# STM32.net
KiCad netlist of a schematic drawn in Altium Designer
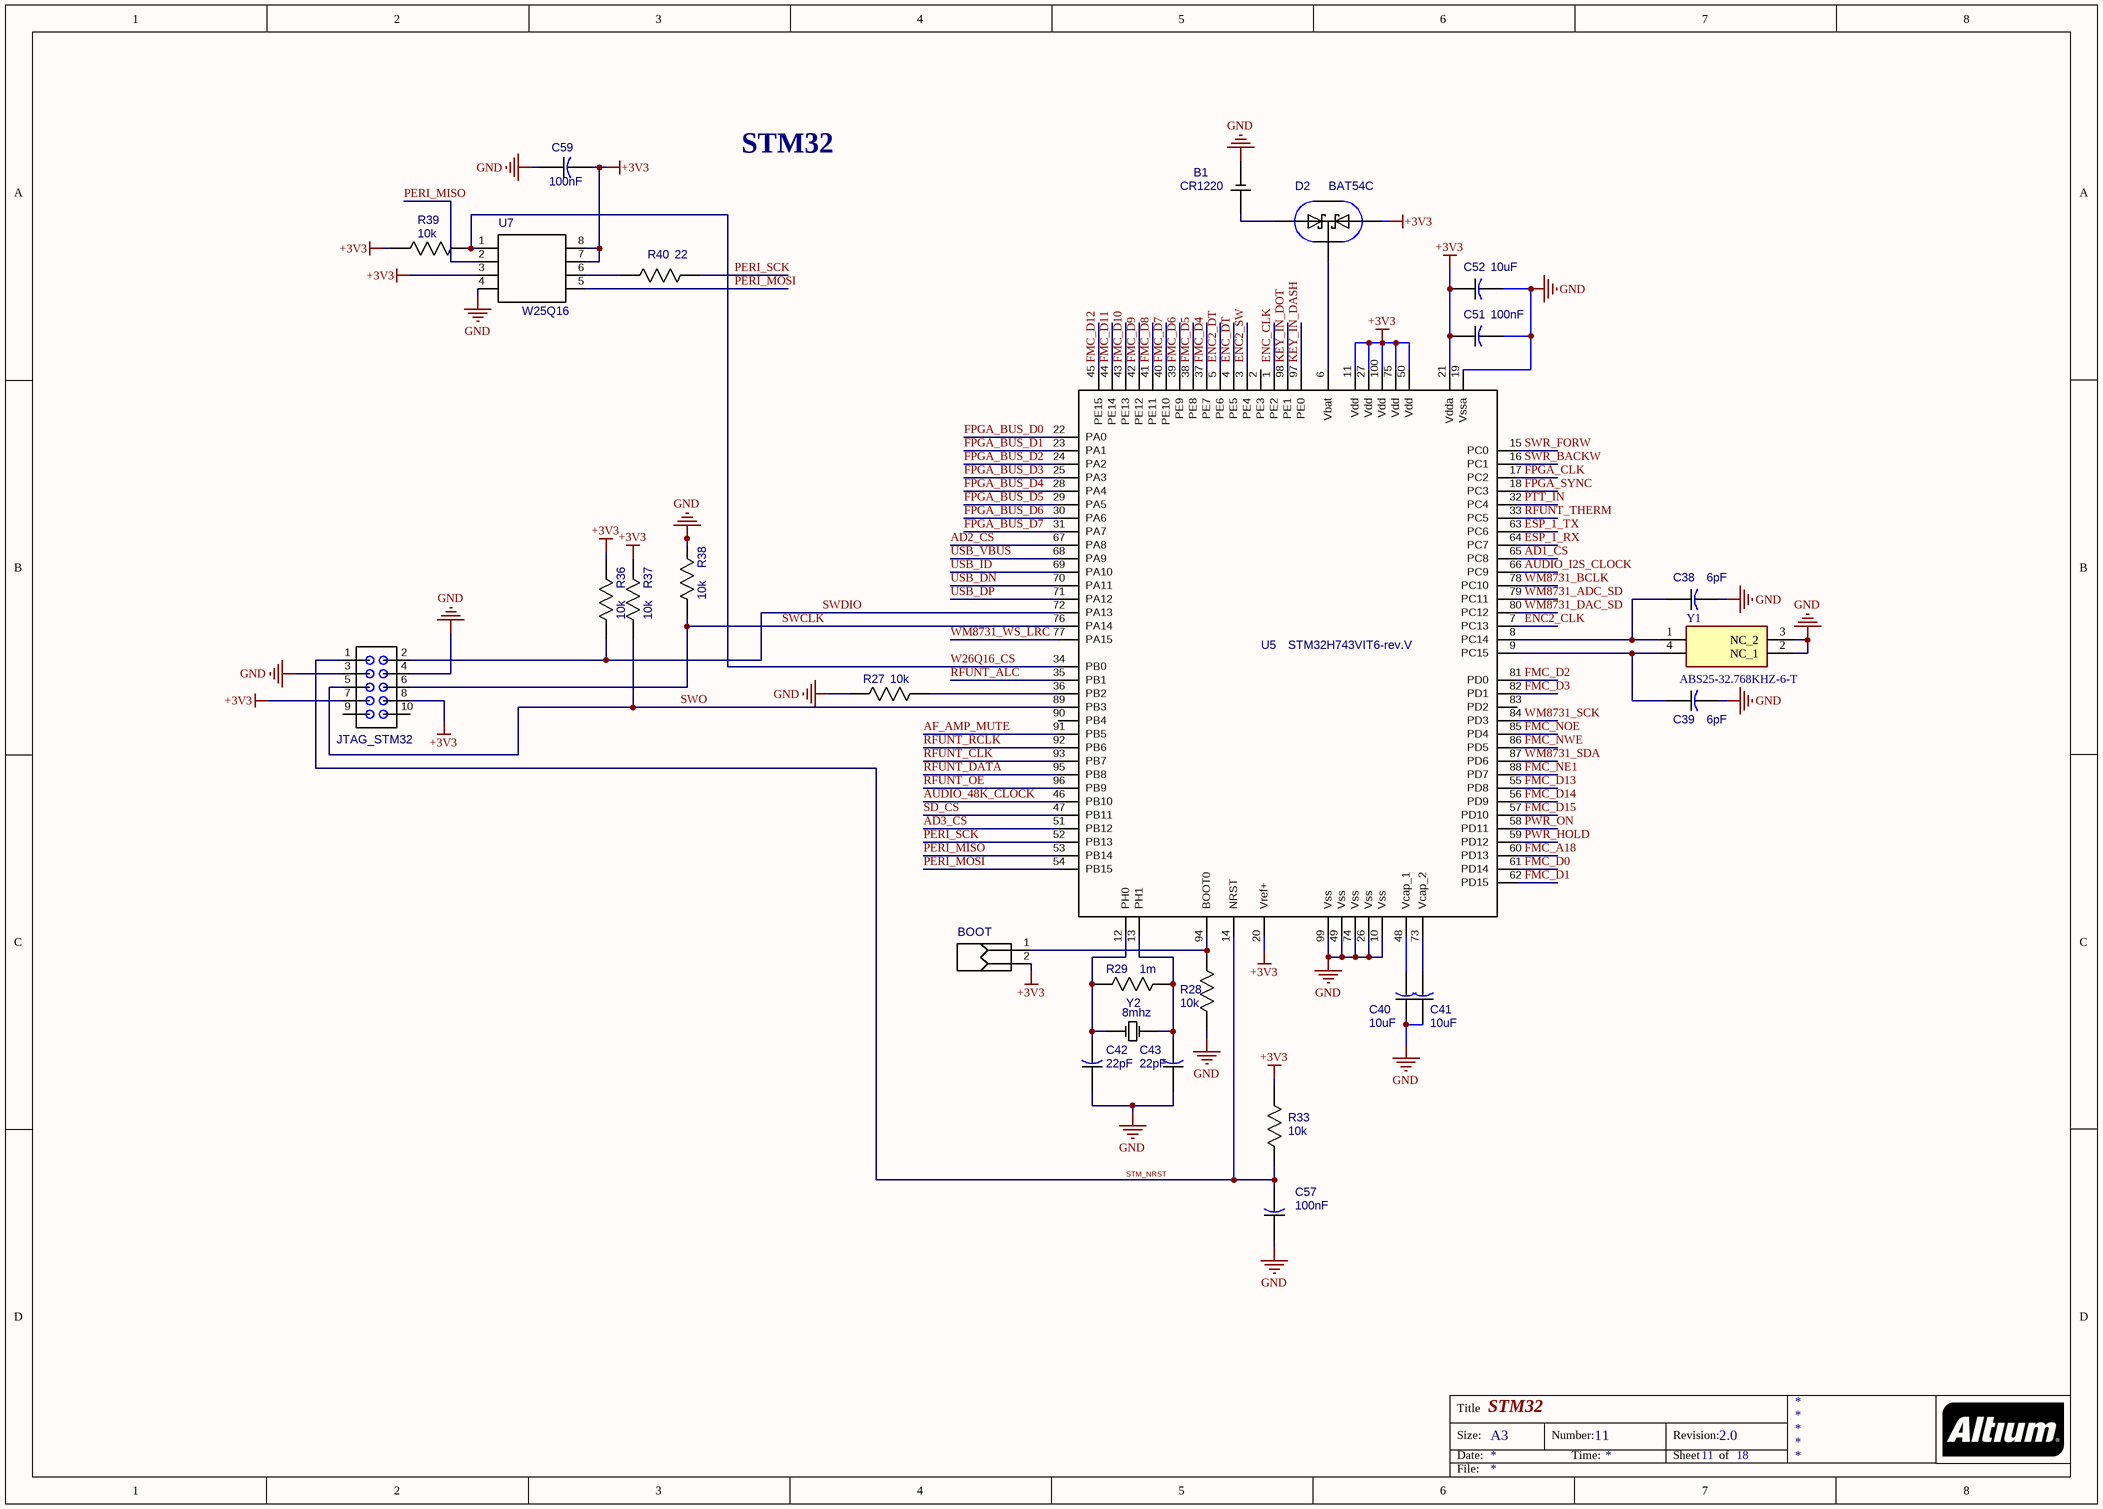
[diagram p0: STM32.SchDoc]

(export (version "E")
  (design (tool "Eeschema 10.0.6"))
  (components
    (comp (ref "B1")
      (value "CR1220")
      (footprint "KLS5-CR1220-01")
      (description "BR1632A/FA")
      (libsource (lib "*") (part "BR1632A/FA"))
    )
    (comp (ref "BOOT")
      (value "~")
      (footprint "51022-0200")
      (description "2 Pin")
      (libsource (lib "*") (part "51022-0200"))
    )
    (comp (ref "C38")
      (value "6pF")
      (footprint "CAP_0805")
      (description "CAP_0805")
      (libsource (lib "*") (part "CAP_0805"))
    )
    (comp (ref "C39")
      (value "6pF")
      (footprint "CAP_0805")
      (description "CAP_0805")
      (libsource (lib "*") (part "CAP_0805"))
    )
    (comp (ref "C40")
      (value "10uF")
      (footprint "CAP_0805")
      (description "CAP_0805")
      (libsource (lib "*") (part "CAP_0805"))
    )
    (comp (ref "C41")
      (value "10uF")
      (footprint "CAP_0805")
      (description "CAP_0805")
      (libsource (lib "*") (part "CAP_0805"))
    )
    (comp (ref "C42")
      (value "22pF")
      (footprint "CAP_0805")
      (description "CAP_0805")
      (libsource (lib "*") (part "CAP_0805"))
    )
    (comp (ref "C43")
      (value "22pF")
      (footprint "CAP_0805")
      (description "CAP_0805")
      (libsource (lib "*") (part "CAP_0805"))
    )
    (comp (ref "C51")
      (value "100nF")
      (footprint "CAP_0805")
      (description "CAP_0805")
      (libsource (lib "*") (part "CAP_0805"))
    )
    (comp (ref "C52")
      (value "10uF")
      (footprint "CAP_0805")
      (description "CAP_0805")
      (libsource (lib "*") (part "CAP_0805"))
    )
    (comp (ref "C57")
      (value "100nF")
      (footprint "CAP_0805")
      (description "CAP_0805")
      (libsource (lib "*") (part "CAP_0805"))
    )
    (comp (ref "C59")
      (value "100nF")
      (footprint "CAP_0805")
      (description "CAP_0805")
      (libsource (lib "*") (part "CAP_0805"))
    )
    (comp (ref "D2") (value "BAT54C") (footprint "BAT54C") (libsource (lib "*") (part "BAT54C")))
    (comp (ref "JTAG_STM32")
      (value "~")
      (footprint "IDC10")
      (description "2*5 Pin")
      (libsource (lib "*") (part "IDC10"))
    )
    (comp (ref "R27")
      (value "10k")
      (footprint "RES_0805")
      (description "RES_0805")
      (libsource (lib "*") (part "RES_0805"))
    )
    (comp (ref "R28")
      (value "10k")
      (footprint "RES_0805")
      (description "RES_0805")
      (libsource (lib "*") (part "RES_0805"))
    )
    (comp (ref "R29")
      (value "1m")
      (footprint "RES_0805")
      (description "RES_0805")
      (libsource (lib "*") (part "RES_0805"))
    )
    (comp (ref "R33")
      (value "10k")
      (footprint "RES_0805")
      (description "RES_0805")
      (libsource (lib "*") (part "RES_0805"))
    )
    (comp (ref "R36")
      (value "10k")
      (footprint "RES_0805")
      (description "RES_0805")
      (libsource (lib "*") (part "RES_0805"))
    )
    (comp (ref "R37")
      (value "10k")
      (footprint "RES_0805")
      (description "RES_0805")
      (libsource (lib "*") (part "RES_0805"))
    )
    (comp (ref "R38")
      (value "10k")
      (footprint "RES_0805")
      (description "RES_0805")
      (libsource (lib "*") (part "RES_0805"))
    )
    (comp (ref "R39")
      (value "10k")
      (footprint "RES_0805")
      (description "RES_0805")
      (libsource (lib "*") (part "RES_0805"))
    )
    (comp (ref "R40")
      (value "22")
      (footprint "RES_0805")
      (description "RES_0805")
      (libsource (lib "*") (part "RES_0805"))
    )
    (comp (ref "U5")
      (value "STM32H743VIT6-rev.V")
      (footprint "STM32H743VIT6")
      (description "STM32H743VIT6")
      (libsource (lib "*") (part "STM32H743VIT6"))
    )
    (comp (ref "U7") (value "W25Q16") (footprint "W25Q16") (libsource (lib "*") (part "W25Q16")))
    (comp (ref "Y1")
      (value "ABS25-32.768KHZ-6-T")
      (footprint "SamacSys:ABS25")
      (description "Crystal or Oscillator")
      (fields
        (field (name "MOUSER PART NUMBER") "815-ABS25-32.768K6-T")
        (field (name "RS PART NUMBER") "1712795P")
      )
      (libsource (lib "*") (part "ABS25-32.768KHZ-6-T"))
    )
    (comp (ref "Y2")
      (value "8mhz")
      (footprint "ECS-200-20-1")
      (description "ECS-200-20-1")
      (libsource (lib "*") (part "ECS-200-20-1"))
    )
  )
  (nets
    (net (code "1") (name "+3V3") (class "Default")
      (node (ref "BOOT") (pin "2") (pinfunction "2_2") (pintype "passive"))
      (node (ref "C51") (pin "1") (pinfunction "1_1") (pintype "passive"))
      (node (ref "C52") (pin "1") (pinfunction "1_1") (pintype "passive"))
      (node (ref "C59") (pin "2") (pinfunction "2_2") (pintype "passive"))
      (node (ref "D2") (pin "1") (pinfunction "(A1)_1") (pintype "passive"))
      (node (ref "JTAG_STM32") (pin "7") (pinfunction "7_7") (pintype "passive"))
      (node (ref "JTAG_STM32") (pin "8") (pinfunction "8_8") (pintype "passive"))
      (node (ref "R33") (pin "2") (pinfunction "2_2") (pintype "passive"))
      (node (ref "R36") (pin "1") (pinfunction "1_1") (pintype "passive"))
      (node (ref "R37") (pin "1") (pinfunction "1_1") (pintype "passive"))
      (node (ref "R39") (pin "1") (pinfunction "1_1") (pintype "passive"))
      (node (ref "U5") (pin "100") (pinfunction "Vdd_100") (pintype "passive"))
      (node (ref "U5") (pin "11") (pinfunction "Vdd_11") (pintype "passive"))
      (node (ref "U5") (pin "20") (pinfunction "Vref+_20") (pintype "passive"))
      (node (ref "U5") (pin "21") (pinfunction "Vdda_21") (pintype "passive"))
      (node (ref "U5") (pin "27") (pinfunction "Vdd_27") (pintype "passive"))
      (node (ref "U5") (pin "50") (pinfunction "Vdd_50") (pintype "passive"))
      (node (ref "U5") (pin "75") (pinfunction "Vdd_75") (pintype "passive"))
      (node (ref "U7") (pin "3") (pinfunction "WP_3") (pintype "passive"))
      (node (ref "U7") (pin "7") (pinfunction "HOLD_7") (pintype "passive"))
      (node (ref "U7") (pin "8") (pinfunction "VCC_8") (pintype "passive"))
    )
    (net (code "2") (name "/AD1_CS") (class "Default")
      (node (ref "U5") (pin "65") (pinfunction "PC8_65") (pintype "passive"))
    )
    (net (code "3") (name "/AD2_CS") (class "Default")
      (node (ref "U5") (pin "67") (pinfunction "PA8_67") (pintype "passive"))
    )
    (net (code "4") (name "/AD3_CS") (class "Default")
      (node (ref "U5") (pin "51") (pinfunction "PB12_51") (pintype "passive"))
    )
    (net (code "5") (name "/AF_AMP_MUTE") (class "Default")
      (node (ref "U5") (pin "91") (pinfunction "PB5_91") (pintype "passive"))
    )
    (net (code "6") (name "/AUDIO_48K_CLOCK") (class "Default")
      (node (ref "U5") (pin "46") (pinfunction "PB10_46") (pintype "passive"))
    )
    (net (code "7") (name "/AUDIO_I2S_CLOCK") (class "Default")
      (node (ref "U5") (pin "66") (pinfunction "PC9_66") (pintype "passive"))
    )
    (net (code "8") (name "/ENC2_CLK") (class "Default")
      (node (ref "U5") (pin "7") (pinfunction "PC13_7") (pintype "passive"))
    )
    (net (code "9") (name "/ENC2_DT") (class "Default")
      (node (ref "U5") (pin "5") (pinfunction "PE6_5") (pintype "passive"))
    )
    (net (code "10") (name "/ENC2_SW") (class "Default")
      (node (ref "U5") (pin "3") (pinfunction "PE4_3") (pintype "passive"))
    )
    (net (code "11") (name "/ENC_CLK") (class "Default")
      (node (ref "U5") (pin "1") (pinfunction "PE2_1") (pintype "passive"))
    )
    (net (code "12") (name "/ENC_DT") (class "Default")
      (node (ref "U5") (pin "4") (pinfunction "PE5_4") (pintype "passive"))
    )
    (net (code "13") (name "/ESP_1_RX") (class "Default")
      (node (ref "U5") (pin "64") (pinfunction "PC7_64") (pintype "passive"))
    )
    (net (code "14") (name "/ESP_1_TX") (class "Default")
      (node (ref "U5") (pin "63") (pinfunction "PC6_63") (pintype "passive"))
    )
    (net (code "15") (name "/FMC_A18") (class "Default")
      (node (ref "U5") (pin "60") (pinfunction "PD13_60") (pintype "passive"))
    )
    (net (code "16") (name "/FMC_D0") (class "Default")
      (node (ref "U5") (pin "61") (pinfunction "PD14_61") (pintype "passive"))
    )
    (net (code "17") (name "/FMC_D1") (class "Default")
      (node (ref "U5") (pin "62") (pinfunction "PD15_62") (pintype "passive"))
    )
    (net (code "18") (name "/FMC_D2") (class "Default")
      (node (ref "U5") (pin "81") (pinfunction "PD0_81") (pintype "passive"))
    )
    (net (code "19") (name "/FMC_D3") (class "Default")
      (node (ref "U5") (pin "82") (pinfunction "PD1_82") (pintype "passive"))
    )
    (net (code "20") (name "/FMC_D4") (class "Default")
      (node (ref "U5") (pin "37") (pinfunction "PE7_37") (pintype "passive"))
    )
    (net (code "21") (name "/FMC_D5") (class "Default")
      (node (ref "U5") (pin "38") (pinfunction "PE8_38") (pintype "passive"))
    )
    (net (code "22") (name "/FMC_D6") (class "Default")
      (node (ref "U5") (pin "39") (pinfunction "PE9_39") (pintype "passive"))
    )
    (net (code "23") (name "/FMC_D7") (class "Default")
      (node (ref "U5") (pin "40") (pinfunction "PE10_40") (pintype "passive"))
    )
    (net (code "24") (name "/FMC_D8") (class "Default")
      (node (ref "U5") (pin "41") (pinfunction "PE11_41") (pintype "passive"))
    )
    (net (code "25") (name "/FMC_D9") (class "Default")
      (node (ref "U5") (pin "42") (pinfunction "PE12_42") (pintype "passive"))
    )
    (net (code "26") (name "/FMC_D10") (class "Default")
      (node (ref "U5") (pin "43") (pinfunction "PE13_43") (pintype "passive"))
    )
    (net (code "27") (name "/FMC_D11") (class "Default")
      (node (ref "U5") (pin "44") (pinfunction "PE14_44") (pintype "passive"))
    )
    (net (code "28") (name "/FMC_D12") (class "Default")
      (node (ref "U5") (pin "45") (pinfunction "PE15_45") (pintype "passive"))
    )
    (net (code "29") (name "/FMC_D13") (class "Default")
      (node (ref "U5") (pin "55") (pinfunction "PD8_55") (pintype "passive"))
    )
    (net (code "30") (name "/FMC_D14") (class "Default")
      (node (ref "U5") (pin "56") (pinfunction "PD9_56") (pintype "passive"))
    )
    (net (code "31") (name "/FMC_D15") (class "Default")
      (node (ref "U5") (pin "57") (pinfunction "PD10_57") (pintype "passive"))
    )
    (net (code "32") (name "/FMC_NE1") (class "Default")
      (node (ref "U5") (pin "88") (pinfunction "PD7_88") (pintype "passive"))
    )
    (net (code "33") (name "/FMC_NOE") (class "Default")
      (node (ref "U5") (pin "85") (pinfunction "PD4_85") (pintype "passive"))
    )
    (net (code "34") (name "/FMC_NWE") (class "Default")
      (node (ref "U5") (pin "86") (pinfunction "PD5_86") (pintype "passive"))
    )
    (net (code "35") (name "/FPGA_BUS_D0") (class "Default")
      (node (ref "U5") (pin "22") (pinfunction "PA0_22") (pintype "passive"))
    )
    (net (code "36") (name "/FPGA_BUS_D1") (class "Default")
      (node (ref "U5") (pin "23") (pinfunction "PA1_23") (pintype "passive"))
    )
    (net (code "37") (name "/FPGA_BUS_D2") (class "Default")
      (node (ref "U5") (pin "24") (pinfunction "PA2_24") (pintype "passive"))
    )
    (net (code "38") (name "/FPGA_BUS_D3") (class "Default")
      (node (ref "U5") (pin "25") (pinfunction "PA3_25") (pintype "passive"))
    )
    (net (code "39") (name "/FPGA_BUS_D4") (class "Default")
      (node (ref "U5") (pin "28") (pinfunction "PA4_28") (pintype "passive"))
    )
    (net (code "40") (name "/FPGA_BUS_D5") (class "Default")
      (node (ref "U5") (pin "29") (pinfunction "PA5_29") (pintype "passive"))
    )
    (net (code "41") (name "/FPGA_BUS_D6") (class "Default")
      (node (ref "U5") (pin "30") (pinfunction "PA6_30") (pintype "passive"))
    )
    (net (code "42") (name "/FPGA_BUS_D7") (class "Default")
      (node (ref "U5") (pin "31") (pinfunction "PA7_31") (pintype "passive"))
    )
    (net (code "43") (name "/FPGA_CLK") (class "Default")
      (node (ref "U5") (pin "17") (pinfunction "PC2_17") (pintype "passive"))
    )
    (net (code "44") (name "/FPGA_SYNC") (class "Default")
      (node (ref "U5") (pin "18") (pinfunction "PC3_18") (pintype "passive"))
    )
    (net (code "45") (name "/KEY_IN_DASH") (class "Default")
      (node (ref "U5") (pin "97") (pinfunction "PE0_97") (pintype "passive"))
    )
    (net (code "46") (name "/KEY_IN_DOT") (class "Default")
      (node (ref "U5") (pin "98") (pinfunction "PE1_98") (pintype "passive"))
    )
    (net (code "47") (name "/PERI_MISO") (class "Default")
      (node (ref "U5") (pin "53") (pinfunction "PB14_53") (pintype "passive"))
      (node (ref "U7") (pin "2") (pinfunction "SO_2") (pintype "passive"))
    )
    (net (code "48") (name "/PERI_MOSI") (class "Default")
      (node (ref "U5") (pin "54") (pinfunction "PB15_54") (pintype "passive"))
      (node (ref "U7") (pin "5") (pinfunction "SI_5") (pintype "passive"))
    )
    (net (code "49") (name "/PERI_SCK") (class "Default")
      (node (ref "R40") (pin "2") (pinfunction "2_2") (pintype "passive"))
      (node (ref "U5") (pin "52") (pinfunction "PB13_52") (pintype "passive"))
    )
    (net (code "50") (name "/PTT_IN") (class "Default")
      (node (ref "U5") (pin "32") (pinfunction "PC4_32") (pintype "passive"))
    )
    (net (code "51") (name "/PWR_HOLD") (class "Default")
      (node (ref "U5") (pin "59") (pinfunction "PD12_59") (pintype "passive"))
    )
    (net (code "52") (name "/PWR_ON") (class "Default")
      (node (ref "U5") (pin "58") (pinfunction "PD11_58") (pintype "passive"))
    )
    (net (code "53") (name "/RFUNT_ALC") (class "Default")
      (node (ref "U5") (pin "35") (pinfunction "PB1_35") (pintype "passive"))
    )
    (net (code "54") (name "/RFUNT_CLK") (class "Default")
      (node (ref "U5") (pin "93") (pinfunction "PB7_93") (pintype "passive"))
    )
    (net (code "55") (name "/RFUNT_DATA") (class "Default")
      (node (ref "U5") (pin "95") (pinfunction "PB8_95") (pintype "passive"))
    )
    (net (code "56") (name "/RFUNT_OE") (class "Default")
      (node (ref "U5") (pin "96") (pinfunction "PB9_96") (pintype "passive"))
    )
    (net (code "57") (name "/RFUNT_RCLK") (class "Default")
      (node (ref "U5") (pin "92") (pinfunction "PB6_92") (pintype "passive"))
    )
    (net (code "58") (name "/RFUNT_THERM") (class "Default")
      (node (ref "U5") (pin "33") (pinfunction "PC5_33") (pintype "passive"))
    )
    (net (code "59") (name "/SD_CS") (class "Default")
      (node (ref "U5") (pin "47") (pinfunction "PB11_47") (pintype "passive"))
    )
    (net (code "60") (name "/STM_NRST") (class "Default")
      (node (ref "C57") (pin "2") (pinfunction "2_2") (pintype "passive"))
      (node (ref "JTAG_STM32") (pin "1") (pinfunction "1_1") (pintype "passive"))
      (node (ref "R33") (pin "1") (pinfunction "1_1") (pintype "passive"))
      (node (ref "U5") (pin "14") (pinfunction "NRST_14") (pintype "passive"))
    )
    (net (code "61") (name "/SWCLK") (class "Default")
      (node (ref "JTAG_STM32") (pin "6") (pinfunction "6_6") (pintype "passive"))
      (node (ref "R38") (pin "2") (pinfunction "2_2") (pintype "passive"))
      (node (ref "U5") (pin "76") (pinfunction "PA14_76") (pintype "passive"))
    )
    (net (code "62") (name "/SWDIO") (class "Default")
      (node (ref "JTAG_STM32") (pin "2") (pinfunction "2_2") (pintype "passive"))
      (node (ref "R36") (pin "2") (pinfunction "2_2") (pintype "passive"))
      (node (ref "U5") (pin "72") (pinfunction "PA13_72") (pintype "passive"))
    )
    (net (code "63") (name "/SWO") (class "Default")
      (node (ref "JTAG_STM32") (pin "5") (pinfunction "5_5") (pintype "passive"))
      (node (ref "R37") (pin "2") (pinfunction "2_2") (pintype "passive"))
      (node (ref "U5") (pin "89") (pinfunction "PB3_89") (pintype "passive"))
    )
    (net (code "64") (name "/SWR_BACKW") (class "Default")
      (node (ref "U5") (pin "16") (pinfunction "PC1_16") (pintype "passive"))
    )
    (net (code "65") (name "/SWR_FORW") (class "Default")
      (node (ref "U5") (pin "15") (pinfunction "PC0_15") (pintype "passive"))
    )
    (net (code "66") (name "/USB_DN") (class "Default")
      (node (ref "U5") (pin "70") (pinfunction "PA11_70") (pintype "passive"))
    )
    (net (code "67") (name "/USB_DP") (class "Default")
      (node (ref "U5") (pin "71") (pinfunction "PA12_71") (pintype "passive"))
    )
    (net (code "68") (name "/USB_ID") (class "Default")
      (node (ref "U5") (pin "69") (pinfunction "PA10_69") (pintype "passive"))
    )
    (net (code "69") (name "/USB_VBUS") (class "Default")
      (node (ref "U5") (pin "68") (pinfunction "PA9_68") (pintype "passive"))
    )
    (net (code "70") (name "/W26Q16_CS") (class "Default")
      (node (ref "R39") (pin "2") (pinfunction "2_2") (pintype "passive"))
      (node (ref "U5") (pin "34") (pinfunction "PB0_34") (pintype "passive"))
      (node (ref "U7") (pin "1") (pinfunction "CS_1") (pintype "passive"))
    )
    (net (code "71") (name "/WM8731_ADC_SD") (class "Default")
      (node (ref "U5") (pin "79") (pinfunction "PC11_79") (pintype "passive"))
    )
    (net (code "72") (name "/WM8731_BCLK") (class "Default")
      (node (ref "U5") (pin "78") (pinfunction "PC10_78") (pintype "passive"))
    )
    (net (code "73") (name "/WM8731_DAC_SD") (class "Default")
      (node (ref "U5") (pin "80") (pinfunction "PC12_80") (pintype "passive"))
    )
    (net (code "74") (name "/WM8731_SCK") (class "Default")
      (node (ref "U5") (pin "84") (pinfunction "PD3_84") (pintype "passive"))
    )
    (net (code "75") (name "/WM8731_SDA") (class "Default")
      (node (ref "U5") (pin "87") (pinfunction "PD6_87") (pintype "passive"))
    )
    (net (code "76") (name "/WM8731_WS_LRC") (class "Default")
      (node (ref "U5") (pin "77") (pinfunction "PA15_77") (pintype "passive"))
    )
    (net (code "77") (name "GND") (class "Default")
      (node (ref "B1") (pin "2") (pinfunction "NEG_2") (pintype "passive"))
      (node (ref "C38") (pin "2") (pinfunction "2_2") (pintype "passive"))
      (node (ref "C39") (pin "2") (pinfunction "2_2") (pintype "passive"))
      (node (ref "C40") (pin "1") (pinfunction "1_1") (pintype "passive"))
      (node (ref "C41") (pin "1") (pinfunction "1_1") (pintype "passive"))
      (node (ref "C42") (pin "1") (pinfunction "1_1") (pintype "passive"))
      (node (ref "C43") (pin "1") (pinfunction "1_1") (pintype "passive"))
      (node (ref "C51") (pin "2") (pinfunction "2_2") (pintype "passive"))
      (node (ref "C52") (pin "2") (pinfunction "2_2") (pintype "passive"))
      (node (ref "C57") (pin "1") (pinfunction "1_1") (pintype "passive"))
      (node (ref "C59") (pin "1") (pinfunction "1_1") (pintype "passive"))
      (node (ref "JTAG_STM32") (pin "3") (pinfunction "3_3") (pintype "passive"))
      (node (ref "JTAG_STM32") (pin "4") (pinfunction "4_4") (pintype "passive"))
      (node (ref "R27") (pin "1") (pinfunction "1_1") (pintype "passive"))
      (node (ref "R28") (pin "1") (pinfunction "1_1") (pintype "passive"))
      (node (ref "R38") (pin "1") (pinfunction "1_1") (pintype "passive"))
      (node (ref "U5") (pin "10") (pinfunction "Vss_10") (pintype "passive"))
      (node (ref "U5") (pin "19") (pinfunction "Vssa_19") (pintype "passive"))
      (node (ref "U5") (pin "26") (pinfunction "Vss_26") (pintype "passive"))
      (node (ref "U5") (pin "49") (pinfunction "Vss_49") (pintype "passive"))
      (node (ref "U5") (pin "74") (pinfunction "Vss_74") (pintype "passive"))
      (node (ref "U5") (pin "99") (pinfunction "Vss_99") (pintype "passive"))
      (node (ref "U7") (pin "4") (pinfunction "GND_4") (pintype "passive"))
      (node (ref "Y1") (pin "2") (pinfunction "NC_1_2") (pintype "passive"))
      (node (ref "Y1") (pin "3") (pinfunction "NC_2_3") (pintype "passive"))
    )
    (net (code "78") (name "Net-(B1-POS)") (class "Default")
      (node (ref "B1") (pin "1") (pinfunction "POS_1") (pintype "passive"))
      (node (ref "D2") (pin "2") (pinfunction "(A2)_2") (pintype "passive"))
    )
    (net (code "79") (name "Net-(D2-(K1),(K2))") (class "Default")
      (node (ref "D2") (pin "3") (pinfunction "(K1),(K2)_3") (pintype "passive"))
      (node (ref "U5") (pin "6") (pinfunction "Vbat_6") (pintype "passive"))
    )
    (net (code "80") (name "Net-(U5-BOOT0)") (class "Default")
      (node (ref "BOOT") (pin "1") (pinfunction "1_1") (pintype "passive"))
      (node (ref "R28") (pin "2") (pinfunction "2_2") (pintype "passive"))
      (node (ref "U5") (pin "94") (pinfunction "BOOT0_94") (pintype "passive"))
    )
    (net (code "81") (name "Net-(U5-PB2)") (class "Default")
      (node (ref "R27") (pin "2") (pinfunction "2_2") (pintype "passive"))
      (node (ref "U5") (pin "36") (pinfunction "PB2_36") (pintype "passive"))
    )
    (net (code "82") (name "Net-(U5-PC14)") (class "Default")
      (node (ref "C38") (pin "1") (pinfunction "1_1") (pintype "passive"))
      (node (ref "U5") (pin "8") (pinfunction "PC14_8") (pintype "passive"))
      (node (ref "Y1") (pin "1") (pinfunction "1_1") (pintype "passive"))
    )
    (net (code "83") (name "Net-(U5-PC15)") (class "Default")
      (node (ref "C39") (pin "1") (pinfunction "1_1") (pintype "passive"))
      (node (ref "U5") (pin "9") (pinfunction "PC15_9") (pintype "passive"))
      (node (ref "Y1") (pin "4") (pinfunction "4_4") (pintype "passive"))
    )
    (net (code "84") (name "Net-(U5-PH0)") (class "Default")
      (node (ref "C42") (pin "2") (pinfunction "2_2") (pintype "passive"))
      (node (ref "R29") (pin "1") (pinfunction "1_1") (pintype "passive"))
      (node (ref "U5") (pin "12") (pinfunction "PH0_12") (pintype "passive"))
      (node (ref "Y2") (pin "1") (pinfunction "OSC1_1") (pintype "passive"))
    )
    (net (code "85") (name "Net-(U5-PH1)") (class "Default")
      (node (ref "C43") (pin "2") (pinfunction "2_2") (pintype "passive"))
      (node (ref "R29") (pin "2") (pinfunction "2_2") (pintype "passive"))
      (node (ref "U5") (pin "13") (pinfunction "PH1_13") (pintype "passive"))
      (node (ref "Y2") (pin "2") (pinfunction "OSC2_2") (pintype "passive"))
    )
    (net (code "86") (name "Net-(U5-Vcap_1)") (class "Default")
      (node (ref "C40") (pin "2") (pinfunction "2_2") (pintype "passive"))
      (node (ref "U5") (pin "48") (pinfunction "Vcap_1_48") (pintype "passive"))
    )
    (net (code "87") (name "Net-(U5-Vcap_2)") (class "Default")
      (node (ref "C41") (pin "2") (pinfunction "2_2") (pintype "passive"))
      (node (ref "U5") (pin "73") (pinfunction "Vcap_2_73") (pintype "passive"))
    )
    (net (code "88") (name "Net-(U7-CLK)") (class "Default")
      (node (ref "R40") (pin "1") (pinfunction "1_1") (pintype "passive"))
      (node (ref "U7") (pin "6") (pinfunction "CLK_6") (pintype "passive"))
    )
    (net (code "89") (name "unconnected-(JTAG_STM32-Pad9)") (class "Default")
      (node (ref "JTAG_STM32") (pin "9") (pinfunction "9_9") (pintype "passive"))
    )
    (net (code "90") (name "unconnected-(JTAG_STM32-Pad10)") (class "Default")
      (node (ref "JTAG_STM32") (pin "10") (pinfunction "10_10") (pintype "passive"))
    )
    (net (code "91") (name "unconnected-(U5-PB4-Pad90)") (class "Default")
      (node (ref "U5") (pin "90") (pinfunction "PB4_90") (pintype "passive"))
    )
    (net (code "92") (name "unconnected-(U5-PD2-Pad83)") (class "Default")
      (node (ref "U5") (pin "83") (pinfunction "PD2_83") (pintype "passive"))
    )
    (net (code "93") (name "unconnected-(U5-PE3-Pad2)") (class "Default")
      (node (ref "U5") (pin "2") (pinfunction "PE3_2") (pintype "passive"))
    )
  )
)
